# BT_atmega_v_1_0.net
KiCad netlist of a schematic drawn in EAGLE
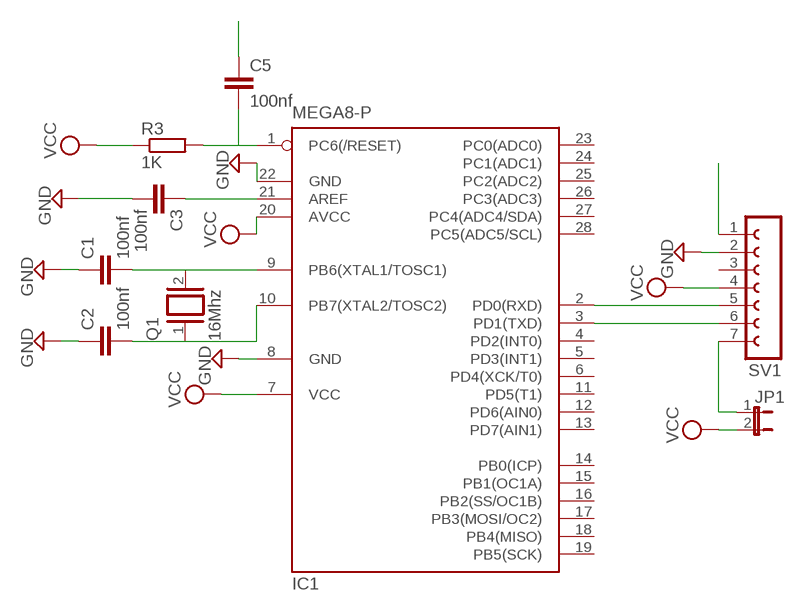
[diagram p0: schematic, sheet 1]

(export (version "E")
  (design (tool "Eeschema 10.0.6"))
  (components
    (comp (ref "C1")
      (value "100nf")
      (footprint "eagle-import:C2.5-2")
      (libsource (lib "eagle-import") (part "C2.5/2"))
    )
    (comp (ref "C2")
      (value "100nf")
      (footprint "eagle-import:C2.5-2")
      (libsource (lib "eagle-import") (part "C2.5/2"))
    )
    (comp (ref "C3")
      (value "100nf")
      (footprint "eagle-import:C2.5-2")
      (libsource (lib "eagle-import") (part "C2.5/2"))
    )
    (comp (ref "C5")
      (value "100nf")
      (footprint "eagle-import:C2.5-2")
      (libsource (lib "eagle-import") (part "C2.5/2"))
    )
    (comp (ref "IC1")
      (value "MEGA8-P")
      (footprint "eagle-import:DIL28-3")
      (libsource (lib "eagle-import") (part "MEGA8-P"))
    )
    (comp (ref "JP1")
      (value "JP1E")
      (footprint "eagle-import:JP1")
      (libsource (lib "eagle-import") (part "JP1E"))
    )
    (comp (ref "Q1")
      (value "16Mhz")
      (footprint "eagle-import:QS")
      (libsource (lib "eagle-import") (part "XTAL/S"))
    )
    (comp (ref "R3")
      (value "1K")
      (footprint "eagle-import:0204_7")
      (libsource (lib "eagle-import") (part "R0204/7"))
    )
    (comp (ref "SV1")
      (value "FE07-1")
      (footprint "eagle-import:FE07")
      (libsource (lib "eagle-import") (part "FE07-1"))
    )
  )
  (nets
    (net (code "1") (name "/BT_RST") (class "Default")
      (node (ref "C5") (pin "1") (pinfunction "1_1") (pintype "passive"))
      (node (ref "SV1") (pin "1") (pinfunction "1_1") (pintype "passive"))
    )
    (net (code "2") (name "GND") (class "Default")
      (node (ref "C1") (pin "1") (pinfunction "1_1") (pintype "passive"))
      (node (ref "C2") (pin "1") (pinfunction "1_1") (pintype "passive"))
      (node (ref "C3") (pin "2") (pinfunction "2_2") (pintype "passive"))
      (node (ref "IC1") (pin "22") (pinfunction "GND_22") (pintype "power_in"))
      (node (ref "IC1") (pin "8") (pinfunction "GND_8") (pintype "power_in"))
      (node (ref "SV1") (pin "2") (pinfunction "2_2") (pintype "passive"))
    )
    (net (code "3") (name "Net-(IC1-AREF)") (class "Default")
      (node (ref "C3") (pin "1") (pinfunction "1_1") (pintype "passive"))
      (node (ref "IC1") (pin "21") (pinfunction "AREF_21") (pintype "passive"))
    )
    (net (code "4") (name "Net-(IC1-PB6(XTAL1{slash}TOSC1))") (class "Default")
      (node (ref "C1") (pin "2") (pinfunction "2_2") (pintype "passive"))
      (node (ref "IC1") (pin "9") (pinfunction "PB6(XTAL1/TOSC1)_9") (pintype "bidirectional"))
      (node (ref "Q1") (pin "2") (pinfunction "2_2") (pintype "passive"))
    )
    (net (code "5") (name "Net-(IC1-PB7(XTAL2{slash}TOSC2))") (class "Default")
      (node (ref "C2") (pin "2") (pinfunction "2_2") (pintype "passive"))
      (node (ref "IC1") (pin "10") (pinfunction "PB7(XTAL2/TOSC2)_10") (pintype "bidirectional"))
      (node (ref "Q1") (pin "1") (pinfunction "1_1") (pintype "passive"))
    )
    (net (code "6") (name "Net-(IC1-PC6({slash}RESET))") (class "Default")
      (node (ref "C5") (pin "2") (pinfunction "2_2") (pintype "passive"))
      (node (ref "IC1") (pin "1") (pinfunction "PC6(/RESET)_1") (pintype "bidirectional"))
      (node (ref "R3") (pin "2") (pinfunction "2_2") (pintype "passive"))
    )
    (net (code "7") (name "Net-(IC1-PD0(RXD))") (class "Default")
      (node (ref "IC1") (pin "2") (pinfunction "PD0(RXD)_2") (pintype "bidirectional"))
      (node (ref "SV1") (pin "5") (pinfunction "5_5") (pintype "passive"))
    )
    (net (code "8") (name "Net-(IC1-PD1(TXD))") (class "Default")
      (node (ref "IC1") (pin "3") (pinfunction "PD1(TXD)_3") (pintype "bidirectional"))
      (node (ref "SV1") (pin "6") (pinfunction "6_6") (pintype "passive"))
    )
    (net (code "9") (name "Net-(JP1-Pad1)") (class "Default")
      (node (ref "JP1") (pin "1") (pinfunction "1_1") (pintype "passive"))
      (node (ref "SV1") (pin "7") (pinfunction "7_7") (pintype "passive"))
    )
    (net (code "10") (name "VCC") (class "Default")
      (node (ref "IC1") (pin "20") (pinfunction "AVCC_20") (pintype "power_in"))
      (node (ref "IC1") (pin "7") (pinfunction "VCC_7") (pintype "power_in"))
      (node (ref "JP1") (pin "2") (pinfunction "2_2") (pintype "passive"))
      (node (ref "R3") (pin "1") (pinfunction "1_1") (pintype "passive"))
      (node (ref "SV1") (pin "4") (pinfunction "4_4") (pintype "passive"))
    )
    (net (code "11") (name "unconnected-(IC1-PB0(ICP)-Pad14)") (class "Default")
      (node (ref "IC1") (pin "14") (pinfunction "PB0(ICP)_14") (pintype "bidirectional"))
    )
    (net (code "12") (name "unconnected-(IC1-PB1(OC1A)-Pad15)") (class "Default")
      (node (ref "IC1") (pin "15") (pinfunction "PB1(OC1A)_15") (pintype "bidirectional"))
    )
    (net (code "13") (name "unconnected-(IC1-PB2(SS{slash}OC1B)-Pad16)") (class "Default")
      (node (ref "IC1") (pin "16") (pinfunction "PB2(SS/OC1B)_16") (pintype "bidirectional"))
    )
    (net (code "14") (name "unconnected-(IC1-PB3(MOSI{slash}OC2)-Pad17)") (class "Default")
      (node (ref "IC1") (pin "17") (pinfunction "PB3(MOSI/OC2)_17") (pintype "bidirectional"))
    )
    (net (code "15") (name "unconnected-(IC1-PB4(MISO)-Pad18)") (class "Default")
      (node (ref "IC1") (pin "18") (pinfunction "PB4(MISO)_18") (pintype "bidirectional"))
    )
    (net (code "16") (name "unconnected-(IC1-PB5(SCK)-Pad19)") (class "Default")
      (node (ref "IC1") (pin "19") (pinfunction "PB5(SCK)_19") (pintype "bidirectional"))
    )
    (net (code "17") (name "unconnected-(IC1-PC0(ADC0)-Pad23)") (class "Default")
      (node (ref "IC1") (pin "23") (pinfunction "PC0(ADC0)_23") (pintype "bidirectional"))
    )
    (net (code "18") (name "unconnected-(IC1-PC1(ADC1)-Pad24)") (class "Default")
      (node (ref "IC1") (pin "24") (pinfunction "PC1(ADC1)_24") (pintype "bidirectional"))
    )
    (net (code "19") (name "unconnected-(IC1-PC2(ADC2)-Pad25)") (class "Default")
      (node (ref "IC1") (pin "25") (pinfunction "PC2(ADC2)_25") (pintype "bidirectional"))
    )
    (net (code "20") (name "unconnected-(IC1-PC3(ADC3)-Pad26)") (class "Default")
      (node (ref "IC1") (pin "26") (pinfunction "PC3(ADC3)_26") (pintype "bidirectional"))
    )
    (net (code "21") (name "unconnected-(IC1-PC4(ADC4{slash}SDA)-Pad27)") (class "Default")
      (node (ref "IC1") (pin "27") (pinfunction "PC4(ADC4/SDA)_27") (pintype "bidirectional"))
    )
    (net (code "22") (name "unconnected-(IC1-PC5(ADC5{slash}SCL)-Pad28)") (class "Default")
      (node (ref "IC1") (pin "28") (pinfunction "PC5(ADC5/SCL)_28") (pintype "bidirectional"))
    )
    (net (code "23") (name "unconnected-(IC1-PD2(INT0)-Pad4)") (class "Default")
      (node (ref "IC1") (pin "4") (pinfunction "PD2(INT0)_4") (pintype "bidirectional"))
    )
    (net (code "24") (name "unconnected-(IC1-PD3(INT1)-Pad5)") (class "Default")
      (node (ref "IC1") (pin "5") (pinfunction "PD3(INT1)_5") (pintype "bidirectional"))
    )
    (net (code "25") (name "unconnected-(IC1-PD4(XCK{slash}T0)-Pad6)") (class "Default")
      (node (ref "IC1") (pin "6") (pinfunction "PD4(XCK/T0)_6") (pintype "bidirectional"))
    )
    (net (code "26") (name "unconnected-(IC1-PD5(T1)-Pad11)") (class "Default")
      (node (ref "IC1") (pin "11") (pinfunction "PD5(T1)_11") (pintype "bidirectional"))
    )
    (net (code "27") (name "unconnected-(IC1-PD6(AIN0)-Pad12)") (class "Default")
      (node (ref "IC1") (pin "12") (pinfunction "PD6(AIN0)_12") (pintype "bidirectional"))
    )
    (net (code "28") (name "unconnected-(IC1-PD7(AIN1)-Pad13)") (class "Default")
      (node (ref "IC1") (pin "13") (pinfunction "PD7(AIN1)_13") (pintype "bidirectional"))
    )
    (net (code "29") (name "unconnected-(SV1-Pad3)") (class "Default")
      (node (ref "SV1") (pin "3") (pinfunction "3_3") (pintype "passive"))
    )
  )
)
